# n7byu_k3ng_rotator_shield.net
KiCad netlist of a schematic drawn in EAGLE
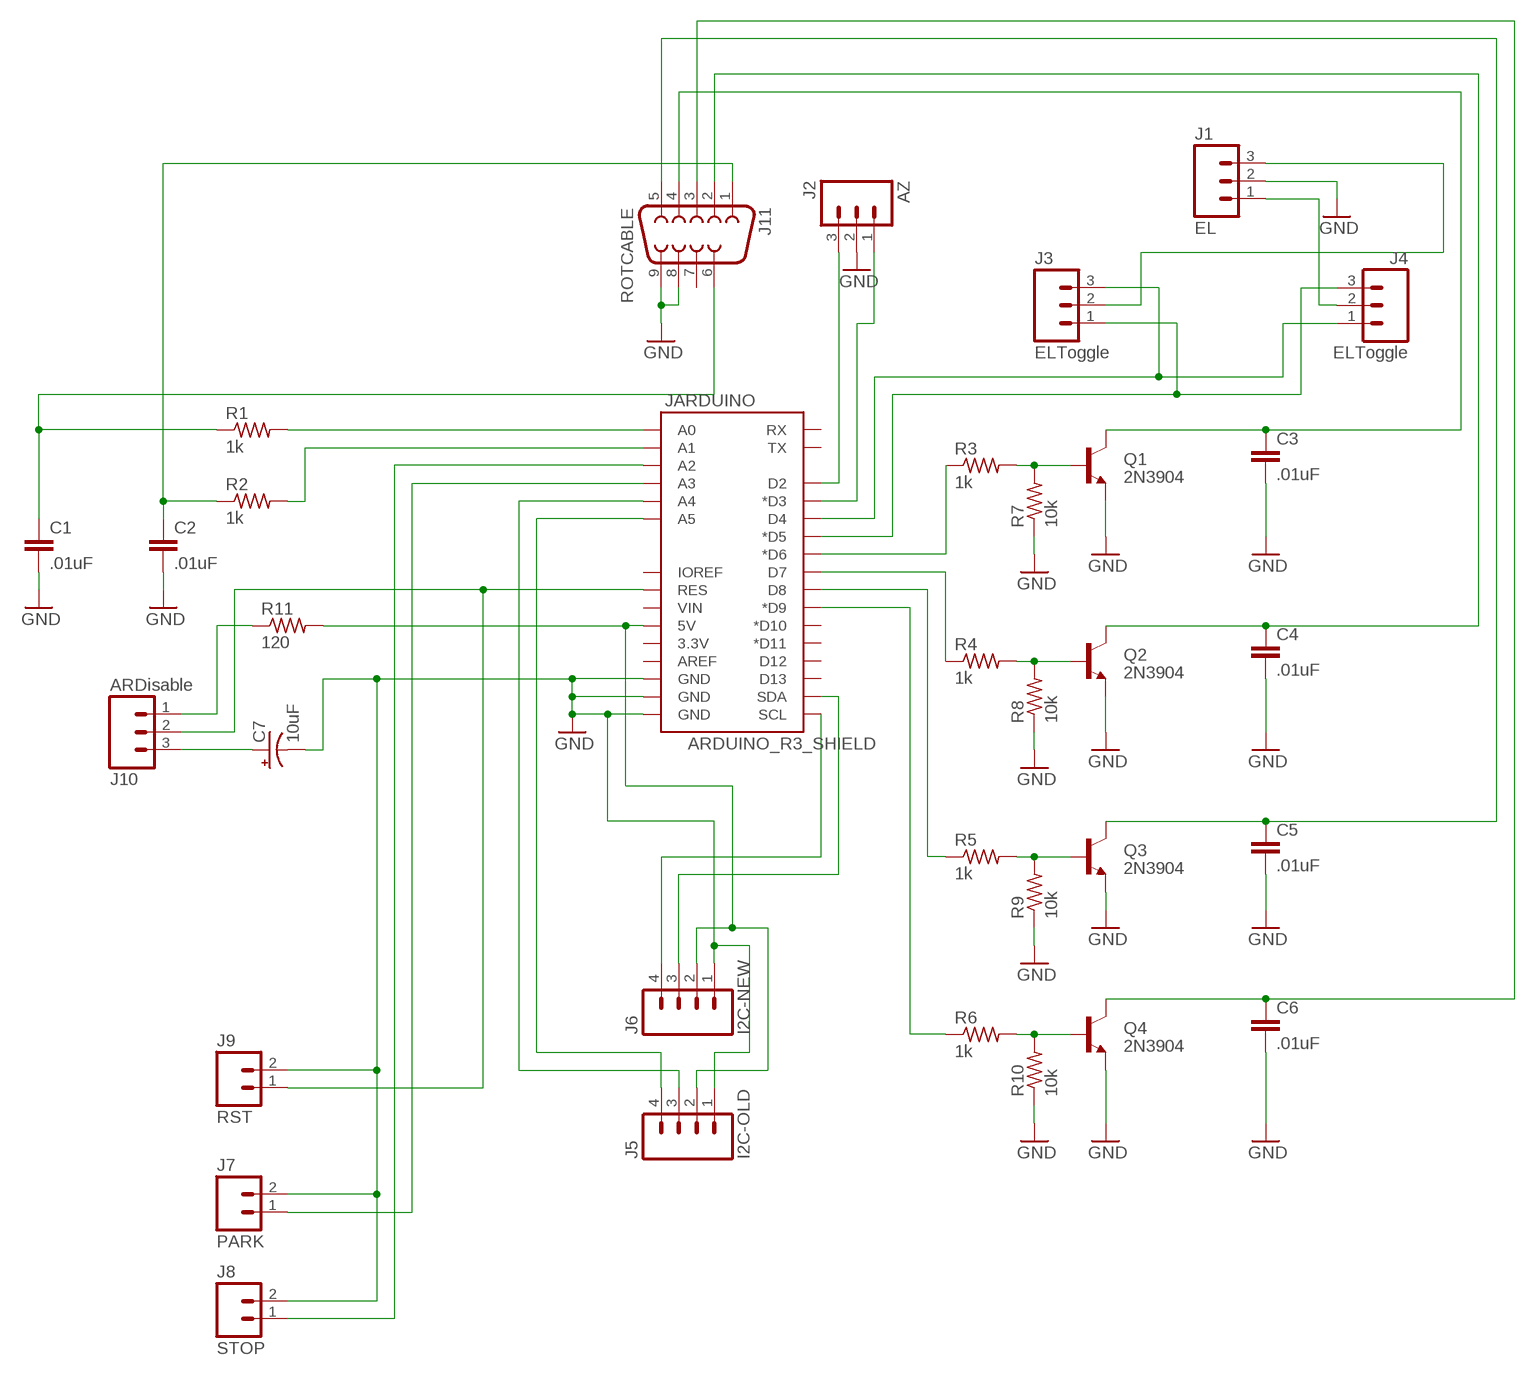
[diagram p0: schematic, sheet 1]

(export (version "E")
  (design (tool "Eeschema 10.0.6"))
  (components
    (comp (ref "C1")
      (value ".01uF")
      (footprint "eagle-import:CAP-PTH-SMALLEZ")
      (libsource (lib "eagle-import") (part "CAPEZ"))
    )
    (comp (ref "C2")
      (value ".01uF")
      (footprint "eagle-import:CAP-PTH-SMALLEZ")
      (libsource (lib "eagle-import") (part "CAPEZ"))
    )
    (comp (ref "C3")
      (value ".01uF")
      (footprint "eagle-import:CAP-PTH-SMALLEZ")
      (libsource (lib "eagle-import") (part "CAPEZ"))
    )
    (comp (ref "C4")
      (value ".01uF")
      (footprint "eagle-import:CAP-PTH-SMALLEZ")
      (libsource (lib "eagle-import") (part "CAPEZ"))
    )
    (comp (ref "C5")
      (value ".01uF")
      (footprint "eagle-import:CAP-PTH-SMALLEZ")
      (libsource (lib "eagle-import") (part "CAPEZ"))
    )
    (comp (ref "C6")
      (value ".01uF")
      (footprint "eagle-import:CAP-PTH-SMALLEZ")
      (libsource (lib "eagle-import") (part "CAPEZ"))
    )
    (comp (ref "C7")
      (value "10uF")
      (footprint "eagle-import:CPOL-RADIAL-100UF-25V")
      (libsource (lib "eagle-import") (part "CAP_POLPTH1"))
    )
    (comp (ref "J1")
      (value "EL")
      (footprint "eagle-import:1X03_LOCK_LONGPADS")
      (libsource (lib "eagle-import") (part "M03LOCK_LONGPADS"))
    )
    (comp (ref "J2")
      (value "AZ")
      (footprint "eagle-import:1X03_LOCK_LONGPADS")
      (libsource (lib "eagle-import") (part "M03LOCK_LONGPADS"))
    )
    (comp (ref "J3")
      (value "ELToggle")
      (footprint "eagle-import:1X03_LOCK_LONGPADS")
      (libsource (lib "eagle-import") (part "M03LOCK_LONGPADS"))
    )
    (comp (ref "J4")
      (value "ELToggle")
      (footprint "eagle-import:1X03_LOCK_LONGPADS")
      (libsource (lib "eagle-import") (part "M03LOCK_LONGPADS"))
    )
    (comp (ref "J5")
      (value "I2C-OLD")
      (footprint "eagle-import:1X04_LOCK_LONGPADS")
      (libsource (lib "eagle-import") (part "M04LOCK_LONGPADS"))
    )
    (comp (ref "J6")
      (value "I2C-NEW")
      (footprint "eagle-import:1X04_LOCK_LONGPADS")
      (libsource (lib "eagle-import") (part "M04LOCK_LONGPADS"))
    )
    (comp (ref "J7")
      (value "PARK")
      (footprint "eagle-import:1X02_LOCK_LONGPADS")
      (libsource (lib "eagle-import") (part "M02LOCK_LONGPADS"))
    )
    (comp (ref "J8")
      (value "STOP")
      (footprint "eagle-import:1X02_LOCK_LONGPADS")
      (libsource (lib "eagle-import") (part "M02LOCK_LONGPADS"))
    )
    (comp (ref "J9")
      (value "RST")
      (footprint "eagle-import:1X02_LOCK_LONGPADS")
      (libsource (lib "eagle-import") (part "M02LOCK_LONGPADS"))
    )
    (comp (ref "J10")
      (value "ARDisable")
      (footprint "eagle-import:1X03_LOCK_LONGPADS")
      (libsource (lib "eagle-import") (part "M03LOCK_LONGPADS"))
    )
    (comp (ref "J11")
      (value "ROTCABLE")
      (footprint "eagle-import:DB9")
      (libsource (lib "eagle-import") (part "DB9FEMALE"))
    )
    (comp (ref "JARDUINO")
      (value "ARDUINO_R3_SHIELD")
      (footprint "eagle-import:UNO_R3_SHIELD")
      (libsource (lib "eagle-import") (part "ARDUINO_R3_SHIELD"))
    )
    (comp (ref "Q1")
      (value "2N3904")
      (footprint "eagle-import:TO-92-EZ")
      (libsource (lib "eagle-import") (part "TRANSISTOR_NPN2N3904-EZ"))
    )
    (comp (ref "Q2")
      (value "2N3904")
      (footprint "eagle-import:TO-92-EZ")
      (libsource (lib "eagle-import") (part "TRANSISTOR_NPN2N3904-EZ"))
    )
    (comp (ref "Q3")
      (value "2N3904")
      (footprint "eagle-import:TO-92-EZ")
      (libsource (lib "eagle-import") (part "TRANSISTOR_NPN2N3904-EZ"))
    )
    (comp (ref "Q4")
      (value "2N3904")
      (footprint "eagle-import:TO-92-EZ")
      (libsource (lib "eagle-import") (part "TRANSISTOR_NPN2N3904-EZ"))
    )
    (comp (ref "R1")
      (value "1k")
      (footprint "eagle-import:0204_7")
      (libsource (lib "eagle-import") (part "R-US_0204/7"))
    )
    (comp (ref "R2")
      (value "1k")
      (footprint "eagle-import:0204_7")
      (libsource (lib "eagle-import") (part "R-US_0204/7"))
    )
    (comp (ref "R3")
      (value "1k")
      (footprint "eagle-import:0204_7")
      (libsource (lib "eagle-import") (part "R-US_0204/7"))
    )
    (comp (ref "R4")
      (value "1k")
      (footprint "eagle-import:0204_7")
      (libsource (lib "eagle-import") (part "R-US_0204/7"))
    )
    (comp (ref "R5")
      (value "1k")
      (footprint "eagle-import:0204_7")
      (libsource (lib "eagle-import") (part "R-US_0204/7"))
    )
    (comp (ref "R6")
      (value "1k")
      (footprint "eagle-import:0204_7")
      (libsource (lib "eagle-import") (part "R-US_0204/7"))
    )
    (comp (ref "R7")
      (value "10k")
      (footprint "eagle-import:0204_7")
      (libsource (lib "eagle-import") (part "R-US_0204/7"))
    )
    (comp (ref "R8")
      (value "10k")
      (footprint "eagle-import:0204_7")
      (libsource (lib "eagle-import") (part "R-US_0204/7"))
    )
    (comp (ref "R9")
      (value "10k")
      (footprint "eagle-import:0204_7")
      (libsource (lib "eagle-import") (part "R-US_0204/7"))
    )
    (comp (ref "R10")
      (value "10k")
      (footprint "eagle-import:0204_7")
      (libsource (lib "eagle-import") (part "R-US_0204/7"))
    )
    (comp (ref "R11")
      (value "120")
      (footprint "eagle-import:0204_7")
      (libsource (lib "eagle-import") (part "R-US_0204/7"))
    )
  )
  (nets
    (net (code "1") (name "GND") (class "Default")
      (node (ref "C1") (pin "2") (pinfunction "2_2") (pintype "passive"))
      (node (ref "C2") (pin "2") (pinfunction "2_2") (pintype "passive"))
      (node (ref "C3") (pin "2") (pinfunction "2_2") (pintype "passive"))
      (node (ref "C4") (pin "2") (pinfunction "2_2") (pintype "passive"))
      (node (ref "C5") (pin "2") (pinfunction "2_2") (pintype "passive"))
      (node (ref "C6") (pin "2") (pinfunction "2_2") (pintype "passive"))
      (node (ref "C7") (pin "2") (pinfunction "-_2") (pintype "passive"))
      (node (ref "J1") (pin "2") (pinfunction "2_2") (pintype "passive"))
      (node (ref "J11") (pin "8") (pinfunction "8_8") (pintype "passive"))
      (node (ref "J11") (pin "9") (pinfunction "9_9") (pintype "passive"))
      (node (ref "J2") (pin "2") (pinfunction "2_2") (pintype "passive"))
      (node (ref "J5") (pin "1") (pinfunction "1_1") (pintype "passive"))
      (node (ref "J6") (pin "1") (pinfunction "1_1") (pintype "passive"))
      (node (ref "J7") (pin "2") (pinfunction "2_2") (pintype "passive"))
      (node (ref "J8") (pin "2") (pinfunction "2_2") (pintype "passive"))
      (node (ref "J9") (pin "2") (pinfunction "2_2") (pintype "passive"))
      (node (ref "JARDUINO") (pin "GND@0") (pinfunction "GND_GND@0") (pintype "bidirectional"))
      (node (ref "JARDUINO") (pin "GND@1") (pinfunction "GND_GND@1") (pintype "bidirectional"))
      (node (ref "JARDUINO") (pin "GND@2") (pinfunction "GND_GND@2") (pintype "bidirectional"))
      (node (ref "Q1") (pin "1") (pinfunction "E_1") (pintype "passive"))
      (node (ref "Q2") (pin "1") (pinfunction "E_1") (pintype "passive"))
      (node (ref "Q3") (pin "1") (pinfunction "E_1") (pintype "passive"))
      (node (ref "Q4") (pin "1") (pinfunction "E_1") (pintype "passive"))
      (node (ref "R10") (pin "1") (pinfunction "1_1") (pintype "passive"))
      (node (ref "R7") (pin "1") (pinfunction "1_1") (pintype "passive"))
      (node (ref "R8") (pin "1") (pinfunction "1_1") (pintype "passive"))
      (node (ref "R9") (pin "1") (pinfunction "1_1") (pintype "passive"))
    )
    (net (code "2") (name "Net-(C1-Pad1)") (class "Default")
      (node (ref "C1") (pin "1") (pinfunction "1_1") (pintype "passive"))
      (node (ref "J11") (pin "6") (pinfunction "6_6") (pintype "passive"))
      (node (ref "R1") (pin "1") (pinfunction "1_1") (pintype "passive"))
    )
    (net (code "3") (name "Net-(C2-Pad1)") (class "Default")
      (node (ref "C2") (pin "1") (pinfunction "1_1") (pintype "passive"))
      (node (ref "J11") (pin "1") (pinfunction "1_1") (pintype "passive"))
      (node (ref "R2") (pin "1") (pinfunction "1_1") (pintype "passive"))
    )
    (net (code "4") (name "Net-(C7-+)") (class "Default")
      (node (ref "C7") (pin "1") (pinfunction "+_1") (pintype "passive"))
      (node (ref "J10") (pin "3") (pinfunction "3_3") (pintype "passive"))
    )
    (net (code "5") (name "Net-(J1-Pad1)") (class "Default")
      (node (ref "J1") (pin "1") (pinfunction "1_1") (pintype "passive"))
      (node (ref "J4") (pin "2") (pinfunction "2_2") (pintype "passive"))
    )
    (net (code "6") (name "Net-(J1-Pad3)") (class "Default")
      (node (ref "J1") (pin "3") (pinfunction "3_3") (pintype "passive"))
      (node (ref "J3") (pin "2") (pinfunction "2_2") (pintype "passive"))
    )
    (net (code "7") (name "Net-(J2-Pad3)") (class "Default")
      (node (ref "J2") (pin "3") (pinfunction "3_3") (pintype "passive"))
      (node (ref "JARDUINO") (pin "D2") (pinfunction "D2_D2") (pintype "bidirectional"))
    )
    (net (code "8") (name "Net-(J3-Pad3)") (class "Default")
      (node (ref "J3") (pin "3") (pinfunction "3_3") (pintype "passive"))
      (node (ref "J4") (pin "1") (pinfunction "1_1") (pintype "passive"))
      (node (ref "JARDUINO") (pin "D4") (pinfunction "D4_D4") (pintype "bidirectional"))
    )
    (net (code "9") (name "Net-(J5-Pad2)") (class "Default")
      (node (ref "J5") (pin "2") (pinfunction "2_2") (pintype "passive"))
      (node (ref "J6") (pin "2") (pinfunction "2_2") (pintype "passive"))
      (node (ref "JARDUINO") (pin "5V") (pinfunction "5V_5V") (pintype "bidirectional"))
      (node (ref "R11") (pin "2") (pinfunction "2_2") (pintype "passive"))
    )
    (net (code "10") (name "Net-(J5-Pad3)") (class "Default")
      (node (ref "J5") (pin "3") (pinfunction "3_3") (pintype "passive"))
      (node (ref "JARDUINO") (pin "A4") (pinfunction "A4_A4") (pintype "bidirectional"))
    )
    (net (code "11") (name "Net-(J5-Pad4)") (class "Default")
      (node (ref "J5") (pin "4") (pinfunction "4_4") (pintype "passive"))
      (node (ref "JARDUINO") (pin "A5") (pinfunction "A5_A5") (pintype "bidirectional"))
    )
    (net (code "12") (name "Net-(J6-Pad3)") (class "Default")
      (node (ref "J6") (pin "3") (pinfunction "3_3") (pintype "passive"))
      (node (ref "JARDUINO") (pin "SDA") (pinfunction "SDA_SDA") (pintype "bidirectional"))
    )
    (net (code "13") (name "Net-(J6-Pad4)") (class "Default")
      (node (ref "J6") (pin "4") (pinfunction "4_4") (pintype "passive"))
      (node (ref "JARDUINO") (pin "SCL") (pinfunction "SCL_SCL") (pintype "bidirectional"))
    )
    (net (code "14") (name "Net-(J7-Pad1)") (class "Default")
      (node (ref "J7") (pin "1") (pinfunction "1_1") (pintype "passive"))
      (node (ref "JARDUINO") (pin "A3") (pinfunction "A3_A3") (pintype "bidirectional"))
    )
    (net (code "15") (name "Net-(J8-Pad1)") (class "Default")
      (node (ref "J8") (pin "1") (pinfunction "1_1") (pintype "passive"))
      (node (ref "JARDUINO") (pin "A2") (pinfunction "A2_A2") (pintype "bidirectional"))
    )
    (net (code "16") (name "Net-(J10-Pad1)") (class "Default")
      (node (ref "J10") (pin "1") (pinfunction "1_1") (pintype "passive"))
      (node (ref "R11") (pin "1") (pinfunction "1_1") (pintype "passive"))
    )
    (net (code "17") (name "Net-(J10-Pad2)") (class "Default")
      (node (ref "J10") (pin "2") (pinfunction "2_2") (pintype "passive"))
      (node (ref "J9") (pin "1") (pinfunction "1_1") (pintype "passive"))
      (node (ref "JARDUINO") (pin "RES") (pinfunction "RES_RES") (pintype "bidirectional"))
    )
    (net (code "18") (name "Net-(JARDUINO-*D3)") (class "Default")
      (node (ref "J2") (pin "1") (pinfunction "1_1") (pintype "passive"))
      (node (ref "JARDUINO") (pin "D3") (pinfunction "*D3_D3") (pintype "bidirectional"))
    )
    (net (code "19") (name "Net-(JARDUINO-*D5)") (class "Default")
      (node (ref "J3") (pin "1") (pinfunction "1_1") (pintype "passive"))
      (node (ref "J4") (pin "3") (pinfunction "3_3") (pintype "passive"))
      (node (ref "JARDUINO") (pin "D5") (pinfunction "*D5_D5") (pintype "bidirectional"))
    )
    (net (code "20") (name "Net-(JARDUINO-*D6)") (class "Default")
      (node (ref "JARDUINO") (pin "D6") (pinfunction "*D6_D6") (pintype "bidirectional"))
      (node (ref "R3") (pin "1") (pinfunction "1_1") (pintype "passive"))
    )
    (net (code "21") (name "Net-(JARDUINO-*D9)") (class "Default")
      (node (ref "JARDUINO") (pin "D9") (pinfunction "*D9_D9") (pintype "bidirectional"))
      (node (ref "R6") (pin "1") (pinfunction "1_1") (pintype "passive"))
    )
    (net (code "22") (name "Net-(JARDUINO-PadA0)") (class "Default")
      (node (ref "JARDUINO") (pin "A0") (pinfunction "A0_A0") (pintype "bidirectional"))
      (node (ref "R1") (pin "2") (pinfunction "2_2") (pintype "passive"))
    )
    (net (code "23") (name "Net-(JARDUINO-PadA1)") (class "Default")
      (node (ref "JARDUINO") (pin "A1") (pinfunction "A1_A1") (pintype "bidirectional"))
      (node (ref "R2") (pin "2") (pinfunction "2_2") (pintype "passive"))
    )
    (net (code "24") (name "Net-(JARDUINO-PadD7)") (class "Default")
      (node (ref "JARDUINO") (pin "D7") (pinfunction "D7_D7") (pintype "bidirectional"))
      (node (ref "R4") (pin "1") (pinfunction "1_1") (pintype "passive"))
    )
    (net (code "25") (name "Net-(JARDUINO-PadD8)") (class "Default")
      (node (ref "JARDUINO") (pin "D8") (pinfunction "D8_D8") (pintype "bidirectional"))
      (node (ref "R5") (pin "1") (pinfunction "1_1") (pintype "passive"))
    )
    (net (code "26") (name "Net-(Q1-B)") (class "Default")
      (node (ref "Q1") (pin "2") (pinfunction "B_2") (pintype "passive"))
      (node (ref "R3") (pin "2") (pinfunction "2_2") (pintype "passive"))
      (node (ref "R7") (pin "2") (pinfunction "2_2") (pintype "passive"))
    )
    (net (code "27") (name "Net-(Q1-C)") (class "Default")
      (node (ref "C3") (pin "1") (pinfunction "1_1") (pintype "passive"))
      (node (ref "J11") (pin "4") (pinfunction "4_4") (pintype "passive"))
      (node (ref "Q1") (pin "3") (pinfunction "C_3") (pintype "passive"))
    )
    (net (code "28") (name "Net-(Q2-B)") (class "Default")
      (node (ref "Q2") (pin "2") (pinfunction "B_2") (pintype "passive"))
      (node (ref "R4") (pin "2") (pinfunction "2_2") (pintype "passive"))
      (node (ref "R8") (pin "2") (pinfunction "2_2") (pintype "passive"))
    )
    (net (code "29") (name "Net-(Q2-C)") (class "Default")
      (node (ref "C4") (pin "1") (pinfunction "1_1") (pintype "passive"))
      (node (ref "J11") (pin "2") (pinfunction "2_2") (pintype "passive"))
      (node (ref "Q2") (pin "3") (pinfunction "C_3") (pintype "passive"))
    )
    (net (code "30") (name "Net-(Q3-B)") (class "Default")
      (node (ref "Q3") (pin "2") (pinfunction "B_2") (pintype "passive"))
      (node (ref "R5") (pin "2") (pinfunction "2_2") (pintype "passive"))
      (node (ref "R9") (pin "2") (pinfunction "2_2") (pintype "passive"))
    )
    (net (code "31") (name "Net-(Q3-C)") (class "Default")
      (node (ref "C5") (pin "1") (pinfunction "1_1") (pintype "passive"))
      (node (ref "J11") (pin "5") (pinfunction "5_5") (pintype "passive"))
      (node (ref "Q3") (pin "3") (pinfunction "C_3") (pintype "passive"))
    )
    (net (code "32") (name "Net-(Q4-B)") (class "Default")
      (node (ref "Q4") (pin "2") (pinfunction "B_2") (pintype "passive"))
      (node (ref "R10") (pin "2") (pinfunction "2_2") (pintype "passive"))
      (node (ref "R6") (pin "2") (pinfunction "2_2") (pintype "passive"))
    )
    (net (code "33") (name "Net-(Q4-C)") (class "Default")
      (node (ref "C6") (pin "1") (pinfunction "1_1") (pintype "passive"))
      (node (ref "J11") (pin "3") (pinfunction "3_3") (pintype "passive"))
      (node (ref "Q4") (pin "3") (pinfunction "C_3") (pintype "passive"))
    )
    (net (code "34") (name "unconnected-(J11-Pad7)") (class "Default")
      (node (ref "J11") (pin "7") (pinfunction "7_7") (pintype "passive"))
    )
    (net (code "35") (name "unconnected-(JARDUINO-*D10-PadD10)") (class "Default")
      (node (ref "JARDUINO") (pin "D10") (pinfunction "*D10_D10") (pintype "bidirectional"))
    )
    (net (code "36") (name "unconnected-(JARDUINO-*D11-PadD11)") (class "Default")
      (node (ref "JARDUINO") (pin "D11") (pinfunction "*D11_D11") (pintype "bidirectional"))
    )
    (net (code "37") (name "unconnected-(JARDUINO-Pad3.3V)") (class "Default")
      (node (ref "JARDUINO") (pin "3.3V") (pinfunction "3.3V_3.3V") (pintype "bidirectional"))
    )
    (net (code "38") (name "unconnected-(JARDUINO-PadAREF)") (class "Default")
      (node (ref "JARDUINO") (pin "AREF") (pinfunction "AREF_AREF") (pintype "bidirectional"))
    )
    (net (code "39") (name "unconnected-(JARDUINO-PadD12)") (class "Default")
      (node (ref "JARDUINO") (pin "D12") (pinfunction "D12_D12") (pintype "bidirectional"))
    )
    (net (code "40") (name "unconnected-(JARDUINO-PadD13)") (class "Default")
      (node (ref "JARDUINO") (pin "D13") (pinfunction "D13_D13") (pintype "bidirectional"))
    )
    (net (code "41") (name "unconnected-(JARDUINO-PadIOREF)") (class "Default")
      (node (ref "JARDUINO") (pin "IOREF") (pinfunction "IOREF_IOREF") (pintype "bidirectional"))
    )
    (net (code "42") (name "unconnected-(JARDUINO-PadRX)") (class "Default")
      (node (ref "JARDUINO") (pin "RX") (pinfunction "RX_RX") (pintype "bidirectional"))
    )
    (net (code "43") (name "unconnected-(JARDUINO-PadTX)") (class "Default")
      (node (ref "JARDUINO") (pin "TX") (pinfunction "TX_TX") (pintype "bidirectional"))
    )
    (net (code "44") (name "unconnected-(JARDUINO-PadVIN)") (class "Default")
      (node (ref "JARDUINO") (pin "VIN") (pinfunction "VIN_VIN") (pintype "bidirectional"))
    )
  )
)
